# PCEmon_PLUS_rev_A.net
KiCad netlist of a schematic drawn in EAGLE
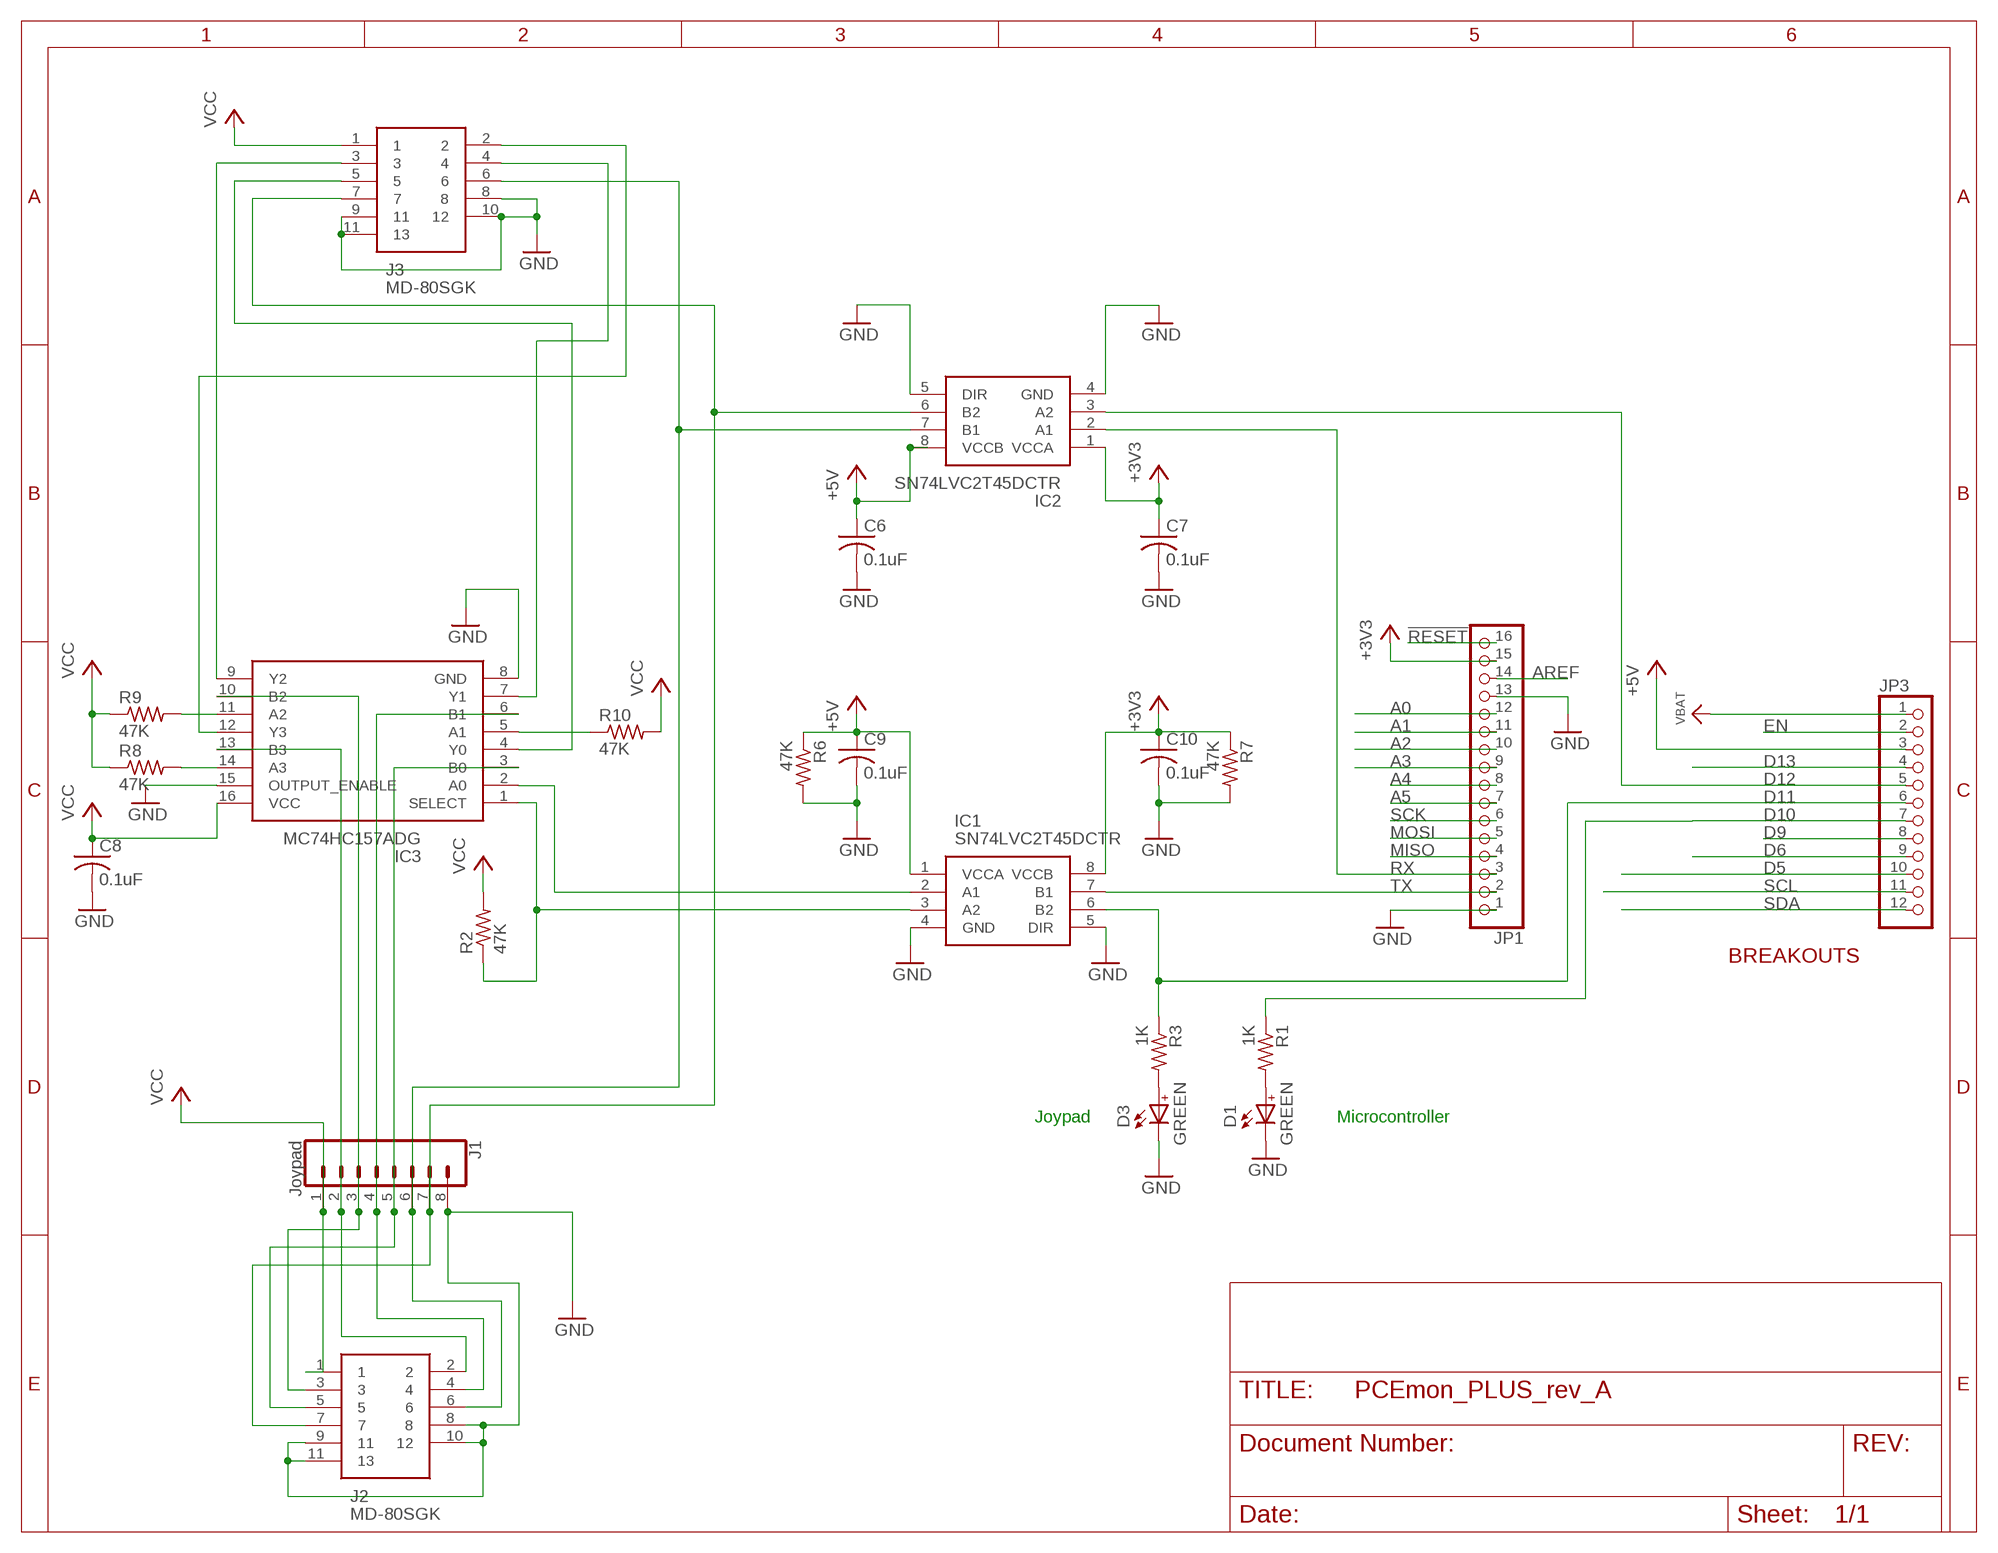
[diagram p0: schematic, sheet 1]

(export (version "E")
  (design (tool "Eeschema 10.0.6"))
  (components
    (comp (ref "C6")
      (value "0.1uF")
      (footprint "eagle-import:C0603")
      (libsource (lib "eagle-import") (part "C-USC0603"))
    )
    (comp (ref "C7")
      (value "0.1uF")
      (footprint "eagle-import:C0603")
      (libsource (lib "eagle-import") (part "C-USC0603"))
    )
    (comp (ref "C8")
      (value "0.1uF")
      (footprint "eagle-import:C0603")
      (libsource (lib "eagle-import") (part "C-USC0603"))
    )
    (comp (ref "C9")
      (value "0.1uF")
      (footprint "eagle-import:C0603")
      (libsource (lib "eagle-import") (part "C-USC0603"))
    )
    (comp (ref "C10")
      (value "0.1uF")
      (footprint "eagle-import:C0603")
      (libsource (lib "eagle-import") (part "C-USC0603"))
    )
    (comp (ref "D1")
      (value "GREEN")
      (footprint "eagle-import:WL-SMCC_0603_R_Y_V")
      (libsource (lib "eagle-import") (part "WL-SMCC_0603_R/V/Y_150060RS73220"))
    )
    (comp (ref "D3")
      (value "GREEN")
      (footprint "eagle-import:WL-SMCC_0603_R_Y_V")
      (libsource (lib "eagle-import") (part "WL-SMCC_0603_R/V/Y_150060RS73220"))
    )
    (comp (ref "IC1")
      (value "SN74LVC2T45DCTR")
      (footprint "eagle-import:SOP65P400X130-8N")
      (fields
        (field (name "MOUSER_PART_NUMBER") "595-SN74LVC2T45DCTR")
        (field (name "RS_PART_NUMBER") "9213022")
      )
      (libsource (lib "eagle-import") (part "SN74LVC2T45DCTR"))
    )
    (comp (ref "IC2")
      (value "SN74LVC2T45DCTR")
      (footprint "eagle-import:SOP65P400X130-8N")
      (fields
        (field (name "MOUSER_PART_NUMBER") "595-SN74LVC2T45DCTR")
        (field (name "RS_PART_NUMBER") "9213022")
      )
      (libsource (lib "eagle-import") (part "SN74LVC2T45DCTR"))
    )
    (comp (ref "IC3")
      (value "MC74HC157ADG")
      (footprint "eagle-import:SOIC127P600X175-16N")
      (fields
        (field (name "MOUSER_PART_NUMBER") "863-MC74HC157ADG")
        (field (name "RS_PART_NUMBER") "8061422P")
      )
      (libsource (lib "eagle-import") (part "MC74HC157ADG"))
    )
    (comp (ref "J1")
      (value "Joypad")
      (footprint "eagle-import:1X08")
      (libsource (lib "eagle-import") (part "CONN_08{dblquote}"))
    )
    (comp (ref "J2")
      (value "MD-80SGK")
      (footprint "eagle-import:MD80SGK")
      (fields (field (name "MOUSER_PART_NUMBER") "490-MD-80SGK"))
      (libsource (lib "eagle-import") (part "MD-80SGK"))
    )
    (comp (ref "J3")
      (value "MD-80SGK")
      (footprint "eagle-import:MD80SGK")
      (fields (field (name "MOUSER_PART_NUMBER") "490-MD-80SGK"))
      (libsource (lib "eagle-import") (part "MD-80SGK"))
    )
    (comp (ref "JP1")
      (value "HEADER-1X16ROUND")
      (footprint "eagle-import:1X16_ROUND")
      (libsource (lib "eagle-import") (part "HEADER-1X16ROUND"))
    )
    (comp (ref "JP3")
      (value "HEADER-1X12")
      (footprint "eagle-import:1X12_ROUND")
      (libsource (lib "eagle-import") (part "HEADER-1X12"))
    )
    (comp (ref "R1")
      (value "1K")
      (footprint "eagle-import:R0603")
      (libsource (lib "eagle-import") (part "R-US_R0603"))
    )
    (comp (ref "R2")
      (value "47K")
      (footprint "eagle-import:R0603")
      (libsource (lib "eagle-import") (part "R-US_R0603"))
    )
    (comp (ref "R3")
      (value "1K")
      (footprint "eagle-import:R0603")
      (libsource (lib "eagle-import") (part "R-US_R0603"))
    )
    (comp (ref "R6")
      (value "47K")
      (footprint "eagle-import:R0603")
      (libsource (lib "eagle-import") (part "R-US_R0603"))
    )
    (comp (ref "R7")
      (value "47K")
      (footprint "eagle-import:R0603")
      (libsource (lib "eagle-import") (part "R-US_R0603"))
    )
    (comp (ref "R8")
      (value "47K")
      (footprint "eagle-import:R0603")
      (libsource (lib "eagle-import") (part "R-US_R0603"))
    )
    (comp (ref "R9")
      (value "47K")
      (footprint "eagle-import:R0603")
      (libsource (lib "eagle-import") (part "R-US_R0603"))
    )
    (comp (ref "R10")
      (value "47K")
      (footprint "eagle-import:R0603")
      (libsource (lib "eagle-import") (part "R-US_R0603"))
    )
  )
  (nets
    (net (code "1") (name "+3V3") (class "Default")
      (node (ref "C10") (pin "1") (pinfunction "1_1") (pintype "passive"))
      (node (ref "C7") (pin "1") (pinfunction "1_1") (pintype "passive"))
      (node (ref "IC1") (pin "8") (pinfunction "VCCB_8") (pintype "power_in"))
      (node (ref "IC2") (pin "1") (pinfunction "VCCA_1") (pintype "power_in"))
      (node (ref "JP1") (pin "15") (pinfunction "15_15") (pintype "passive"))
      (node (ref "R7") (pin "1") (pinfunction "1_1") (pintype "passive"))
    )
    (net (code "2") (name "+5V") (class "Default")
      (node (ref "C6") (pin "1") (pinfunction "1_1") (pintype "passive"))
      (node (ref "C9") (pin "1") (pinfunction "1_1") (pintype "passive"))
      (node (ref "IC1") (pin "1") (pinfunction "VCCA_1") (pintype "power_in"))
      (node (ref "IC2") (pin "8") (pinfunction "VCCB_8") (pintype "power_in"))
      (node (ref "JP3") (pin "3") (pinfunction "3_3") (pintype "passive"))
      (node (ref "R6") (pin "1") (pinfunction "1_1") (pintype "passive"))
    )
    (net (code "3") (name "/A0") (class "Default")
      (node (ref "JP1") (pin "12") (pinfunction "12_12") (pintype "passive"))
    )
    (net (code "4") (name "/A1") (class "Default")
      (node (ref "JP1") (pin "11") (pinfunction "11_11") (pintype "passive"))
    )
    (net (code "5") (name "/A2") (class "Default")
      (node (ref "JP1") (pin "10") (pinfunction "10_10") (pintype "passive"))
    )
    (net (code "6") (name "/A3") (class "Default")
      (node (ref "JP1") (pin "9") (pinfunction "9_9") (pintype "passive"))
    )
    (net (code "7") (name "/A4") (class "Default")
      (node (ref "JP1") (pin "8") (pinfunction "8_8") (pintype "passive"))
    )
    (net (code "8") (name "/A5") (class "Default")
      (node (ref "JP1") (pin "7") (pinfunction "7_7") (pintype "passive"))
    )
    (net (code "9") (name "/AREF") (class "Default")
      (node (ref "JP1") (pin "14") (pinfunction "14_14") (pintype "passive"))
    )
    (net (code "10") (name "/D5") (class "Default")
      (node (ref "JP3") (pin "10") (pinfunction "10_10") (pintype "passive"))
    )
    (net (code "11") (name "/D6") (class "Default")
      (node (ref "JP3") (pin "9") (pinfunction "9_9") (pintype "passive"))
    )
    (net (code "12") (name "/D9") (class "Default")
      (node (ref "JP3") (pin "8") (pinfunction "8_8") (pintype "passive"))
    )
    (net (code "13") (name "/D10") (class "Default")
      (node (ref "JP3") (pin "7") (pinfunction "7_7") (pintype "passive"))
      (node (ref "R1") (pin "1") (pinfunction "1_1") (pintype "passive"))
    )
    (net (code "14") (name "/D11") (class "Default")
      (node (ref "IC1") (pin "6") (pinfunction "B2_6") (pintype "bidirectional"))
      (node (ref "JP3") (pin "6") (pinfunction "6_6") (pintype "passive"))
      (node (ref "R3") (pin "1") (pinfunction "1_1") (pintype "passive"))
    )
    (net (code "15") (name "/D12") (class "Default")
      (node (ref "IC2") (pin "3") (pinfunction "A2_3") (pintype "bidirectional"))
      (node (ref "JP3") (pin "5") (pinfunction "5_5") (pintype "passive"))
    )
    (net (code "16") (name "/D13") (class "Default")
      (node (ref "JP3") (pin "4") (pinfunction "4_4") (pintype "passive"))
    )
    (net (code "17") (name "/EN") (class "Default")
      (node (ref "JP3") (pin "2") (pinfunction "2_2") (pintype "passive"))
    )
    (net (code "18") (name "/MISO") (class "Default")
      (node (ref "JP1") (pin "4") (pinfunction "4_4") (pintype "passive"))
    )
    (net (code "19") (name "/MOSI") (class "Default")
      (node (ref "JP1") (pin "5") (pinfunction "5_5") (pintype "passive"))
    )
    (net (code "20") (name "/RX") (class "Default")
      (node (ref "IC2") (pin "2") (pinfunction "A1_2") (pintype "bidirectional"))
      (node (ref "JP1") (pin "3") (pinfunction "3_3") (pintype "passive"))
    )
    (net (code "21") (name "/SCK") (class "Default")
      (node (ref "JP1") (pin "6") (pinfunction "6_6") (pintype "passive"))
    )
    (net (code "22") (name "/SCL") (class "Default")
      (node (ref "JP3") (pin "11") (pinfunction "11_11") (pintype "passive"))
    )
    (net (code "23") (name "/SDA") (class "Default")
      (node (ref "JP3") (pin "12") (pinfunction "12_12") (pintype "passive"))
    )
    (net (code "24") (name "/TX") (class "Default")
      (node (ref "IC1") (pin "7") (pinfunction "B1_7") (pintype "bidirectional"))
      (node (ref "JP1") (pin "2") (pinfunction "2_2") (pintype "passive"))
    )
    (net (code "25") (name "/~{RESET}") (class "Default")
      (node (ref "JP1") (pin "16") (pinfunction "16_16") (pintype "passive"))
    )
    (net (code "26") (name "GND") (class "Default")
      (node (ref "C10") (pin "2") (pinfunction "2_2") (pintype "passive"))
      (node (ref "C6") (pin "2") (pinfunction "2_2") (pintype "passive"))
      (node (ref "C7") (pin "2") (pinfunction "2_2") (pintype "passive"))
      (node (ref "C8") (pin "2") (pinfunction "2_2") (pintype "passive"))
      (node (ref "C9") (pin "2") (pinfunction "2_2") (pintype "passive"))
      (node (ref "D1") (pin "1") (pinfunction "C_1") (pintype "passive"))
      (node (ref "D3") (pin "1") (pinfunction "C_1") (pintype "passive"))
      (node (ref "IC1") (pin "4") (pinfunction "GND_4") (pintype "power_in"))
      (node (ref "IC1") (pin "5") (pinfunction "DIR_5") (pintype "bidirectional"))
      (node (ref "IC2") (pin "4") (pinfunction "GND_4") (pintype "power_in"))
      (node (ref "IC2") (pin "5") (pinfunction "DIR_5") (pintype "bidirectional"))
      (node (ref "IC3") (pin "15") (pinfunction "OUTPUT_ENABLE_15") (pintype "input"))
      (node (ref "IC3") (pin "8") (pinfunction "GND_8") (pintype "power_in"))
      (node (ref "J1") (pin "8") (pinfunction "8_8") (pintype "passive"))
      (node (ref "J2") (pin "10") (pinfunction "12_10") (pintype "bidirectional"))
      (node (ref "J2") (pin "11") (pinfunction "13_11") (pintype "bidirectional"))
      (node (ref "J2") (pin "8") (pinfunction "8_8") (pintype "bidirectional"))
      (node (ref "J2") (pin "9") (pinfunction "11_9") (pintype "bidirectional"))
      (node (ref "J3") (pin "10") (pinfunction "12_10") (pintype "bidirectional"))
      (node (ref "J3") (pin "11") (pinfunction "13_11") (pintype "bidirectional"))
      (node (ref "J3") (pin "8") (pinfunction "8_8") (pintype "bidirectional"))
      (node (ref "J3") (pin "9") (pinfunction "11_9") (pintype "bidirectional"))
      (node (ref "JP1") (pin "1") (pinfunction "1_1") (pintype "passive"))
      (node (ref "JP1") (pin "13") (pinfunction "13_13") (pintype "passive"))
      (node (ref "R6") (pin "2") (pinfunction "2_2") (pintype "passive"))
      (node (ref "R7") (pin "2") (pinfunction "2_2") (pintype "passive"))
    )
    (net (code "27") (name "Net-(D1-A)") (class "Default")
      (node (ref "D1") (pin "2") (pinfunction "A_2") (pintype "passive"))
      (node (ref "R1") (pin "2") (pinfunction "2_2") (pintype "passive"))
    )
    (net (code "28") (name "Net-(D3-A)") (class "Default")
      (node (ref "D3") (pin "2") (pinfunction "A_2") (pintype "passive"))
      (node (ref "R3") (pin "2") (pinfunction "2_2") (pintype "passive"))
    )
    (net (code "29") (name "Net-(IC1-A1)") (class "Default")
      (node (ref "IC1") (pin "2") (pinfunction "A1_2") (pintype "bidirectional"))
      (node (ref "IC3") (pin "2") (pinfunction "A0_2") (pintype "input"))
    )
    (net (code "30") (name "Net-(IC1-A2)") (class "Default")
      (node (ref "IC1") (pin "3") (pinfunction "A2_3") (pintype "bidirectional"))
      (node (ref "IC3") (pin "1") (pinfunction "SELECT_1") (pintype "input"))
      (node (ref "R2") (pin "1") (pinfunction "1_1") (pintype "passive"))
    )
    (net (code "31") (name "Net-(IC2-B1)") (class "Default")
      (node (ref "IC2") (pin "7") (pinfunction "B1_7") (pintype "bidirectional"))
      (node (ref "J1") (pin "6") (pinfunction "6_6") (pintype "passive"))
      (node (ref "J2") (pin "6") (pinfunction "6_6") (pintype "bidirectional"))
      (node (ref "J3") (pin "6") (pinfunction "6_6") (pintype "bidirectional"))
    )
    (net (code "32") (name "Net-(IC2-B2)") (class "Default")
      (node (ref "IC2") (pin "6") (pinfunction "B2_6") (pintype "bidirectional"))
      (node (ref "J1") (pin "7") (pinfunction "7_7") (pintype "passive"))
      (node (ref "J2") (pin "7") (pinfunction "7_7") (pintype "bidirectional"))
      (node (ref "J3") (pin "7") (pinfunction "7_7") (pintype "bidirectional"))
    )
    (net (code "33") (name "Net-(IC3-A1)") (class "Default")
      (node (ref "IC3") (pin "5") (pinfunction "A1_5") (pintype "input"))
      (node (ref "R10") (pin "1") (pinfunction "1_1") (pintype "passive"))
    )
    (net (code "34") (name "Net-(IC3-A2)") (class "Default")
      (node (ref "IC3") (pin "11") (pinfunction "A2_11") (pintype "input"))
      (node (ref "R9") (pin "2") (pinfunction "2_2") (pintype "passive"))
    )
    (net (code "35") (name "Net-(IC3-A3)") (class "Default")
      (node (ref "IC3") (pin "14") (pinfunction "A3_14") (pintype "input"))
      (node (ref "R8") (pin "2") (pinfunction "2_2") (pintype "passive"))
    )
    (net (code "36") (name "Net-(IC3-B0)") (class "Default")
      (node (ref "IC3") (pin "3") (pinfunction "B0_3") (pintype "input"))
      (node (ref "J1") (pin "5") (pinfunction "5_5") (pintype "passive"))
      (node (ref "J2") (pin "5") (pinfunction "5_5") (pintype "bidirectional"))
    )
    (net (code "37") (name "Net-(IC3-B1)") (class "Default")
      (node (ref "IC3") (pin "6") (pinfunction "B1_6") (pintype "input"))
      (node (ref "J1") (pin "4") (pinfunction "4_4") (pintype "passive"))
      (node (ref "J2") (pin "4") (pinfunction "4_4") (pintype "bidirectional"))
    )
    (net (code "38") (name "Net-(IC3-B2)") (class "Default")
      (node (ref "IC3") (pin "10") (pinfunction "B2_10") (pintype "input"))
      (node (ref "J1") (pin "3") (pinfunction "3_3") (pintype "passive"))
      (node (ref "J2") (pin "3") (pinfunction "3_3") (pintype "bidirectional"))
    )
    (net (code "39") (name "Net-(IC3-B3)") (class "Default")
      (node (ref "IC3") (pin "13") (pinfunction "B3_13") (pintype "input"))
      (node (ref "J1") (pin "2") (pinfunction "2_2") (pintype "passive"))
      (node (ref "J2") (pin "2") (pinfunction "2_2") (pintype "bidirectional"))
    )
    (net (code "40") (name "Net-(IC3-Y0)") (class "Default")
      (node (ref "IC3") (pin "4") (pinfunction "Y0_4") (pintype "output"))
      (node (ref "J3") (pin "5") (pinfunction "5_5") (pintype "bidirectional"))
    )
    (net (code "41") (name "Net-(IC3-Y1)") (class "Default")
      (node (ref "IC3") (pin "7") (pinfunction "Y1_7") (pintype "output"))
      (node (ref "J3") (pin "4") (pinfunction "4_4") (pintype "bidirectional"))
    )
    (net (code "42") (name "Net-(IC3-Y2)") (class "Default")
      (node (ref "IC3") (pin "9") (pinfunction "Y2_9") (pintype "output"))
      (node (ref "J3") (pin "3") (pinfunction "3_3") (pintype "bidirectional"))
    )
    (net (code "43") (name "Net-(IC3-Y3)") (class "Default")
      (node (ref "IC3") (pin "12") (pinfunction "Y3_12") (pintype "output"))
      (node (ref "J3") (pin "2") (pinfunction "2_2") (pintype "bidirectional"))
    )
    (net (code "44") (name "VBAT") (class "Default")
      (node (ref "JP3") (pin "1") (pinfunction "1_1") (pintype "passive"))
    )
    (net (code "45") (name "VCC") (class "Default")
      (node (ref "C8") (pin "1") (pinfunction "1_1") (pintype "passive"))
      (node (ref "IC3") (pin "16") (pinfunction "VCC_16") (pintype "power_in"))
      (node (ref "J1") (pin "1") (pinfunction "1_1") (pintype "passive"))
      (node (ref "J2") (pin "1") (pinfunction "1_1") (pintype "bidirectional"))
      (node (ref "J3") (pin "1") (pinfunction "1_1") (pintype "bidirectional"))
      (node (ref "R10") (pin "2") (pinfunction "2_2") (pintype "passive"))
      (node (ref "R2") (pin "2") (pinfunction "2_2") (pintype "passive"))
      (node (ref "R8") (pin "1") (pinfunction "1_1") (pintype "passive"))
      (node (ref "R9") (pin "1") (pinfunction "1_1") (pintype "passive"))
    )
  )
)
